# like-a-g35.net
KiCad netlist of a schematic drawn in EAGLE
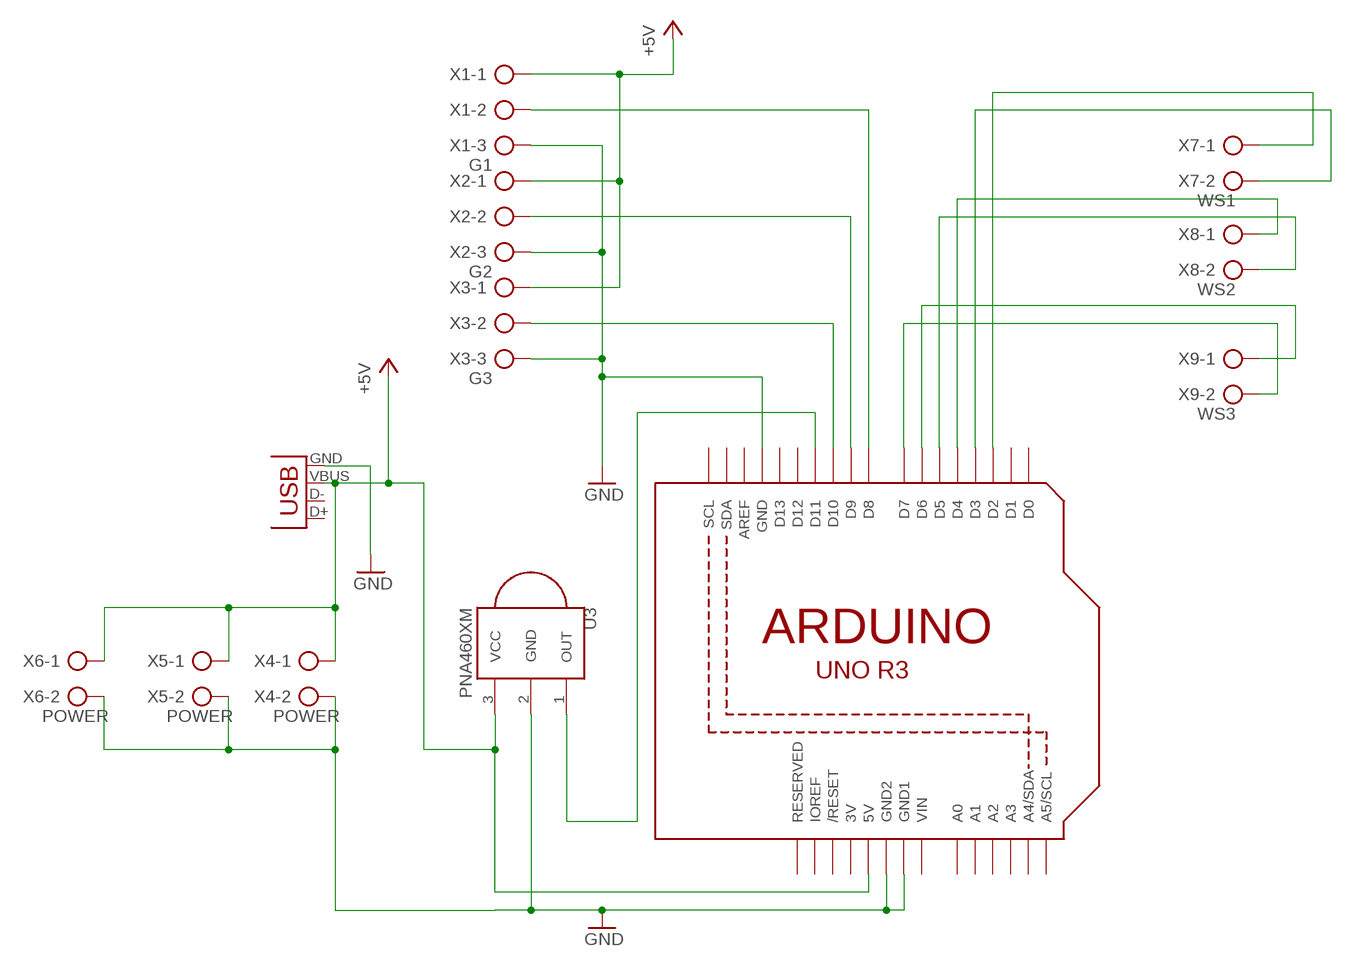
[diagram p0: schematic, sheet 1]

(export (version "E")
  (design (tool "Eeschema 10.0.6"))
  (components
    (comp (ref "U1")
      (value "ARDUINOR3-DIMENSION")
      (footprint "eagle-import:ARDUINOR3")
      (libsource (lib "eagle-import") (part "ARDUINOR3-DIMENSION"))
    )
    (comp (ref "U2")
      (value "FCI_8193_MICRO_USB")
      (footprint "eagle-import:FCI_MICRO_USB_8193")
      (libsource (lib "eagle-import") (part "FCI_8193_MICRO_USB"))
    )
    (comp (ref "U3")
      (value "PNA460XM")
      (footprint "eagle-import:PNA460XM")
      (libsource (lib "eagle-import") (part "PNA460XM"))
    )
    (comp (ref "X1")
      (value "G1")
      (footprint "eagle-import:AK300_3")
      (libsource (lib "eagle-import") (part "AK300/3"))
    )
    (comp (ref "X2")
      (value "G2")
      (footprint "eagle-import:AK300_3")
      (libsource (lib "eagle-import") (part "AK300/3"))
    )
    (comp (ref "X3")
      (value "G3")
      (footprint "eagle-import:AK300_3")
      (libsource (lib "eagle-import") (part "AK300/3"))
    )
    (comp (ref "X4")
      (value "POWER")
      (footprint "eagle-import:AK300_2")
      (libsource (lib "eagle-import") (part "AK300/2"))
    )
    (comp (ref "X5")
      (value "POWER")
      (footprint "eagle-import:AK300_2")
      (fields (field (name "OC_FARNELL") "unknown") (field (name "OC_NEWARK") "unknown"))
      (libsource (lib "eagle-import") (part "AK300/2"))
    )
    (comp (ref "X6")
      (value "POWER")
      (footprint "eagle-import:AK300_2")
      (fields (field (name "OC_FARNELL") "unknown") (field (name "OC_NEWARK") "unknown"))
      (libsource (lib "eagle-import") (part "AK300/2"))
    )
    (comp (ref "X7")
      (value "WS1")
      (footprint "eagle-import:AK300_2")
      (fields (field (name "OC_FARNELL") "unknown") (field (name "OC_NEWARK") "unknown"))
      (libsource (lib "eagle-import") (part "AK300/2"))
    )
    (comp (ref "X8")
      (value "WS2")
      (footprint "eagle-import:AK300_2")
      (fields (field (name "OC_FARNELL") "unknown") (field (name "OC_NEWARK") "unknown"))
      (libsource (lib "eagle-import") (part "AK300/2"))
    )
    (comp (ref "X9")
      (value "WS3")
      (footprint "eagle-import:AK300_2")
      (fields (field (name "OC_FARNELL") "unknown") (field (name "OC_NEWARK") "unknown"))
      (libsource (lib "eagle-import") (part "AK300/2"))
    )
  )
  (nets
    (net (code "1") (name "+5V") (class "Default")
      (node (ref "U1") (pin "5V") (pinfunction "5V_5V") (pintype "power_in"))
      (node (ref "U2") (pin "VBUS") (pinfunction "VBUS_VBUS") (pintype "bidirectional"))
      (node (ref "U3") (pin "3") (pinfunction "VCC_3") (pintype "power_in"))
      (node (ref "X1") (pin "1") (pinfunction "KL_1") (pintype "passive"))
      (node (ref "X2") (pin "1") (pinfunction "KL_1") (pintype "passive"))
      (node (ref "X3") (pin "1") (pinfunction "KL_1") (pintype "passive"))
      (node (ref "X4") (pin "1") (pinfunction "KL_1") (pintype "passive"))
      (node (ref "X5") (pin "1") (pinfunction "KL_1") (pintype "passive"))
      (node (ref "X6") (pin "1") (pinfunction "KL_1") (pintype "passive"))
    )
    (net (code "2") (name "/3V") (class "Default")
      (node (ref "U1") (pin "3V") (pinfunction "3V_3V") (pintype "power_in"))
    )
    (net (code "3") (name "/VIN") (class "Default")
      (node (ref "U1") (pin "VIN") (pinfunction "VIN_VIN") (pintype "power_in"))
    )
    (net (code "4") (name "GND") (class "Default")
      (node (ref "U1") (pin "GND") (pinfunction "GND_GND") (pintype "power_in"))
      (node (ref "U1") (pin "GND1") (pinfunction "GND1_GND1") (pintype "power_in"))
      (node (ref "U1") (pin "GND2") (pinfunction "GND2_GND2") (pintype "power_in"))
      (node (ref "U2") (pin "GND") (pinfunction "GND_GND") (pintype "bidirectional"))
      (node (ref "U3") (pin "2") (pinfunction "GND_2") (pintype "power_in"))
      (node (ref "X1") (pin "3") (pinfunction "KL_3") (pintype "passive"))
      (node (ref "X2") (pin "3") (pinfunction "KL_3") (pintype "passive"))
      (node (ref "X3") (pin "3") (pinfunction "KL_3") (pintype "passive"))
      (node (ref "X4") (pin "2") (pinfunction "KL_2") (pintype "passive"))
      (node (ref "X5") (pin "2") (pinfunction "KL_2") (pintype "passive"))
      (node (ref "X6") (pin "2") (pinfunction "KL_2") (pintype "passive"))
    )
    (net (code "5") (name "Net-(U3-OUT)") (class "Default")
      (node (ref "U1") (pin "D11") (pinfunction "D11_D11") (pintype "bidirectional"))
      (node (ref "U3") (pin "1") (pinfunction "OUT_1") (pintype "output"))
    )
    (net (code "6") (name "Net-(X1B-KL)") (class "Default")
      (node (ref "U1") (pin "D8") (pinfunction "D8_D8") (pintype "bidirectional"))
      (node (ref "X1") (pin "2") (pinfunction "KL_2") (pintype "passive"))
    )
    (net (code "7") (name "Net-(X2B-KL)") (class "Default")
      (node (ref "U1") (pin "D9") (pinfunction "D9_D9") (pintype "bidirectional"))
      (node (ref "X2") (pin "2") (pinfunction "KL_2") (pintype "passive"))
    )
    (net (code "8") (name "Net-(X3B-KL)") (class "Default")
      (node (ref "U1") (pin "D10") (pinfunction "D10_D10") (pintype "bidirectional"))
      (node (ref "X3") (pin "2") (pinfunction "KL_2") (pintype "passive"))
    )
    (net (code "9") (name "Net-(X7A-KL)") (class "Default")
      (node (ref "U1") (pin "D2") (pinfunction "D2_D2") (pintype "bidirectional"))
      (node (ref "X7") (pin "1") (pinfunction "KL_1") (pintype "passive"))
    )
    (net (code "10") (name "Net-(X7B-KL)") (class "Default")
      (node (ref "U1") (pin "D3") (pinfunction "D3_D3") (pintype "bidirectional"))
      (node (ref "X7") (pin "2") (pinfunction "KL_2") (pintype "passive"))
    )
    (net (code "11") (name "Net-(X8A-KL)") (class "Default")
      (node (ref "U1") (pin "D4") (pinfunction "D4_D4") (pintype "bidirectional"))
      (node (ref "X8") (pin "1") (pinfunction "KL_1") (pintype "passive"))
    )
    (net (code "12") (name "Net-(X8B-KL)") (class "Default")
      (node (ref "U1") (pin "D5") (pinfunction "D5_D5") (pintype "bidirectional"))
      (node (ref "X8") (pin "2") (pinfunction "KL_2") (pintype "passive"))
    )
    (net (code "13") (name "Net-(X9A-KL)") (class "Default")
      (node (ref "U1") (pin "D6") (pinfunction "D6_D6") (pintype "bidirectional"))
      (node (ref "X9") (pin "1") (pinfunction "KL_1") (pintype "passive"))
    )
    (net (code "14") (name "Net-(X9B-KL)") (class "Default")
      (node (ref "U1") (pin "D7") (pinfunction "D7_D7") (pintype "bidirectional"))
      (node (ref "X9") (pin "2") (pinfunction "KL_2") (pintype "passive"))
    )
    (net (code "15") (name "unconnected-(U1-A4{slash}SDA-PadA4)") (class "Default")
      (node (ref "U1") (pin "A4") (pinfunction "A4/SDA_A4") (pintype "bidirectional"))
    )
    (net (code "16") (name "unconnected-(U1-A5{slash}SCL-PadA5)") (class "Default")
      (node (ref "U1") (pin "A5") (pinfunction "A5/SCL_A5") (pintype "bidirectional"))
    )
    (net (code "17") (name "unconnected-(U1-PadA0)") (class "Default")
      (node (ref "U1") (pin "A0") (pinfunction "A0_A0") (pintype "bidirectional"))
    )
    (net (code "18") (name "unconnected-(U1-PadA1)") (class "Default")
      (node (ref "U1") (pin "A1") (pinfunction "A1_A1") (pintype "bidirectional"))
    )
    (net (code "19") (name "unconnected-(U1-PadA2)") (class "Default")
      (node (ref "U1") (pin "A2") (pinfunction "A2_A2") (pintype "bidirectional"))
    )
    (net (code "20") (name "unconnected-(U1-PadA3)") (class "Default")
      (node (ref "U1") (pin "A3") (pinfunction "A3_A3") (pintype "bidirectional"))
    )
    (net (code "21") (name "unconnected-(U1-PadAREF)") (class "Default")
      (node (ref "U1") (pin "AREF") (pinfunction "AREF_AREF") (pintype "bidirectional"))
    )
    (net (code "22") (name "unconnected-(U1-PadD0)") (class "Default")
      (node (ref "U1") (pin "D0") (pinfunction "D0_D0") (pintype "bidirectional"))
    )
    (net (code "23") (name "unconnected-(U1-PadD1)") (class "Default")
      (node (ref "U1") (pin "D1") (pinfunction "D1_D1") (pintype "bidirectional"))
    )
    (net (code "24") (name "unconnected-(U1-PadD12)") (class "Default")
      (node (ref "U1") (pin "D12") (pinfunction "D12_D12") (pintype "bidirectional"))
    )
    (net (code "25") (name "unconnected-(U1-PadD13)") (class "Default")
      (node (ref "U1") (pin "D13") (pinfunction "D13_D13") (pintype "bidirectional"))
    )
    (net (code "26") (name "unconnected-(U1-PadIOREF)") (class "Default")
      (node (ref "U1") (pin "IOREF") (pinfunction "IOREF_IOREF") (pintype "output"))
    )
    (net (code "27") (name "unconnected-(U1-PadRESERVED)") (class "Default")
      (node (ref "U1") (pin "RESERVED") (pinfunction "RESERVED_RESERVED") (pintype "no_connect"))
    )
    (net (code "28") (name "unconnected-(U1-PadSCL)") (class "Default")
      (node (ref "U1") (pin "SCL") (pinfunction "SCL_SCL") (pintype "bidirectional"))
    )
    (net (code "29") (name "unconnected-(U1-PadSDA)") (class "Default")
      (node (ref "U1") (pin "SDA") (pinfunction "SDA_SDA") (pintype "bidirectional"))
    )
    (net (code "30") (name "unconnected-(U1-{slash}RESET-PadRESET)") (class "Default")
      (node (ref "U1") (pin "RESET") (pinfunction "/RESET_RESET") (pintype "bidirectional"))
    )
    (net (code "31") (name "unconnected-(U2-PadD+)") (class "Default")
      (node (ref "U2") (pin "D+") (pinfunction "D+_D+") (pintype "bidirectional"))
    )
    (net (code "32") (name "unconnected-(U2-PadD-)") (class "Default")
      (node (ref "U2") (pin "D-") (pinfunction "D-_D-") (pintype "bidirectional"))
    )
  )
)
